# Shematic_servo_light.net
KiCad netlist of a schematic drawn in Altium Designer
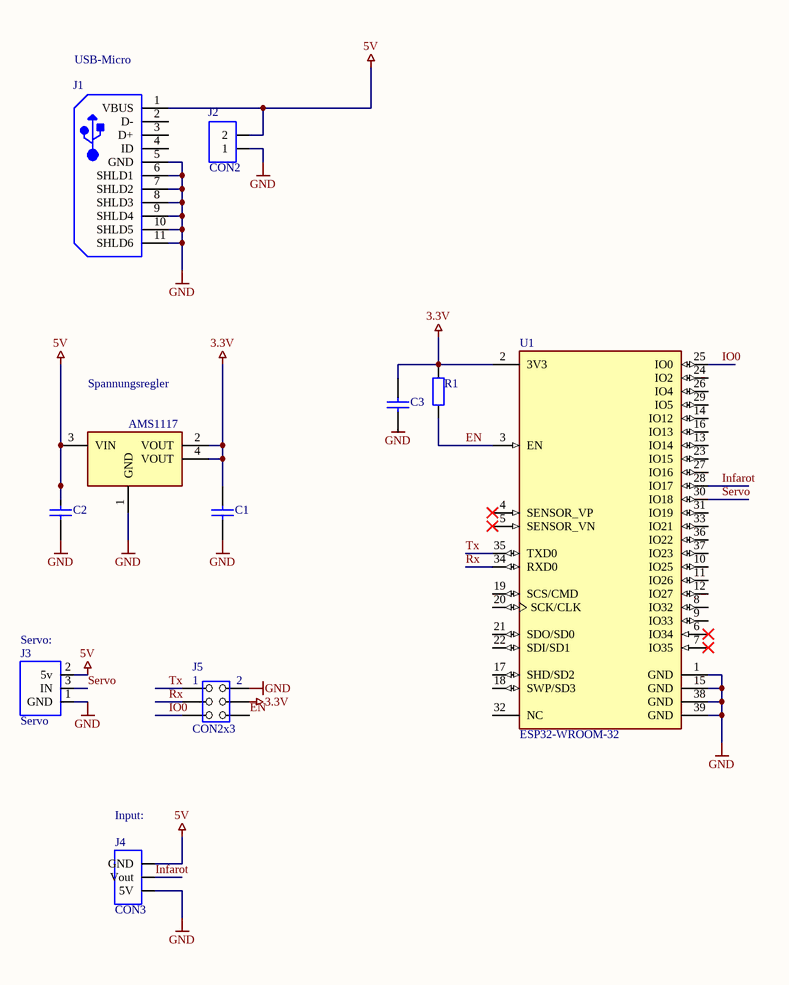
[diagram p0: Shematic_servo_light.SchDoc]

(export (version "E")
  (design (tool "Eeschema 10.0.6"))
  (components
    (comp (ref "C1")
      (value "Cap Ceramic")
      (footprint "0805C")
      (description "Kondensator")
      (libsource (lib "HTL Lib") (part "Cap Ceramic"))
    )
    (comp (ref "C2")
      (value "Cap Ceramic")
      (footprint "0805C")
      (description "Kondensator")
      (libsource (lib "HTL Lib") (part "Cap Ceramic"))
    )
    (comp (ref "C3")
      (value "Cap Ceramic")
      (footprint "0805C")
      (description "Kondensator")
      (libsource (lib "HTL Lib") (part "Cap Ceramic"))
    )
    (comp (ref "J1")
      (value "USB-Micro")
      (footprint "USB-MICRO-B_V - RZEP_CN")
      (description "Right Angle Female Type AB Micro USB Connector, 30 V, 1.8 A, -30 to 85 degC, RoHS, Tape and Reel")
      (fields (field (name "MANUFACTURER") "Molex"))
      (libsource (lib "Rz_RevB") (part "USB_CMP-2000-05610-1"))
    )
    (comp (ref "J2")
      (value "CON2")
      (footprint "SIP-2")
      (description "Stecker")
      (libsource (lib "HTL-sym-2021_04") (part "CON2"))
    )
    (comp (ref "J3")
      (value "Servo")
      (footprint "Sip-3")
      (description "Stecker")
      (libsource (lib "HTL-sym-2021_04") (part "Servo"))
    )
    (comp (ref "J4")
      (value "CON3")
      (footprint "Sip-3")
      (description "Stecker")
      (libsource (lib "HTL Lib") (part "CON3"))
    )
    (comp (ref "J5")
      (value "CON2x3")
      (footprint "PFOSTEN_2x3")
      (description "Stecker")
      (libsource (lib "HTL Lib") (part "CON2x3"))
    )
    (comp (ref "R1")
      (value "Resistor")
      (footprint "0805R")
      (description "Widerstand")
      (libsource (lib "HTL Lib") (part "Resistor"))
    )
    (comp (ref "U1")
      (value "ESP32-WROOM-32")
      (footprint "MODULE_ESP32-WROOM-32")
      (fields (field (name "MF") "Espressif Systems"))
      (libsource (lib "Rz_RevB") (part "ESP32-WROOM-32"))
    )
    (comp (ref "U2")
      (value "AMS1117")
      (footprint "FP-ams1117-IPC_A")
      (libsource (lib "Rz_RevB") (part "AMS1117"))
    )
  )
  (nets
    (net (code "1") (name "/EN") (class "Default")
      (node (ref "J5") (pin "6") (pinfunction "EN_6") (pintype "passive"))
      (node (ref "R1") (pin "2") (pinfunction "2_2") (pintype "passive"))
      (node (ref "U1") (pin "3") (pinfunction "EN_3") (pintype "input"))
    )
    (net (code "2") (name "/IO0") (class "Default")
      (node (ref "J5") (pin "5") (pinfunction "IO0_5") (pintype "passive"))
      (node (ref "U1") (pin "25") (pinfunction "IO0_25") (pintype "bidirectional"))
    )
    (net (code "3") (name "/Infarot") (class "Default")
      (node (ref "J4") (pin "2") (pinfunction "Vout_2") (pintype "passive"))
      (node (ref "U1") (pin "28") (pinfunction "IO17_28") (pintype "bidirectional"))
    )
    (net (code "4") (name "/Rx") (class "Default")
      (node (ref "J5") (pin "3") (pinfunction "Rx_3") (pintype "passive"))
      (node (ref "U1") (pin "34") (pinfunction "RXD0_34") (pintype "bidirectional"))
    )
    (net (code "5") (name "/Servo") (class "Default")
      (node (ref "J3") (pin "3") (pinfunction "IN_3") (pintype "passive"))
      (node (ref "U1") (pin "30") (pinfunction "IO18_30") (pintype "bidirectional"))
    )
    (net (code "6") (name "/Tx") (class "Default")
      (node (ref "J5") (pin "1") (pinfunction "Tx_1") (pintype "passive"))
      (node (ref "U1") (pin "35") (pinfunction "TXD0_35") (pintype "bidirectional"))
    )
    (net (code "7") (name "3.3V") (class "Default")
      (node (ref "C1") (pin "2") (pinfunction "2_2") (pintype "passive"))
      (node (ref "C3") (pin "2") (pinfunction "2_2") (pintype "passive"))
      (node (ref "J5") (pin "4") (pinfunction "3V3_4") (pintype "passive"))
      (node (ref "R1") (pin "1") (pinfunction "1_1") (pintype "passive"))
      (node (ref "U1") (pin "2") (pinfunction "3V3_2") (pintype "power_in"))
      (node (ref "U2") (pin "2") (pinfunction "VOUT_2") (pintype "passive"))
      (node (ref "U2") (pin "4") (pinfunction "VOUT_4") (pintype "passive"))
    )
    (net (code "8") (name "5V") (class "Default")
      (node (ref "C2") (pin "2") (pinfunction "2_2") (pintype "passive"))
      (node (ref "J1") (pin "1") (pinfunction "VBUS_1") (pintype "passive"))
      (node (ref "J2") (pin "2") (pinfunction "2_2") (pintype "passive"))
      (node (ref "J3") (pin "2") (pinfunction "5v_2") (pintype "passive"))
      (node (ref "J4") (pin "3") (pinfunction "GND_3") (pintype "passive"))
      (node (ref "U2") (pin "3") (pinfunction "VIN_3") (pintype "power_in"))
    )
    (net (code "9") (name "GND") (class "Default")
      (node (ref "C1") (pin "1") (pinfunction "1_1") (pintype "passive"))
      (node (ref "C2") (pin "1") (pinfunction "1_1") (pintype "passive"))
      (node (ref "J1") (pin "10") (pinfunction "SHLD5_10") (pintype "passive"))
      (node (ref "J1") (pin "11") (pinfunction "SHLD6_11") (pintype "passive"))
      (node (ref "J1") (pin "5") (pinfunction "GND_5") (pintype "passive"))
      (node (ref "J1") (pin "6") (pinfunction "SHLD1_6") (pintype "passive"))
      (node (ref "J1") (pin "7") (pinfunction "SHLD2_7") (pintype "passive"))
      (node (ref "J1") (pin "8") (pinfunction "SHLD3_8") (pintype "passive"))
      (node (ref "J1") (pin "9") (pinfunction "SHLD4_9") (pintype "passive"))
      (node (ref "J2") (pin "1") (pinfunction "1_1") (pintype "passive"))
      (node (ref "J3") (pin "1") (pinfunction "GND_1") (pintype "passive"))
      (node (ref "J4") (pin "1") (pinfunction "5V_1") (pintype "passive"))
      (node (ref "J5") (pin "2") (pinfunction "GND_2") (pintype "passive"))
      (node (ref "U1") (pin "1") (pinfunction "GND_1") (pintype "power_in"))
      (node (ref "U1") (pin "15") (pinfunction "GND_15") (pintype "power_in"))
      (node (ref "U1") (pin "38") (pinfunction "GND_38") (pintype "power_in"))
      (node (ref "U1") (pin "39") (pinfunction "GND_39") (pintype "power_in"))
      (node (ref "U2") (pin "1") (pinfunction "GND_1") (pintype "power_in"))
    )
    (net (code "10") (name "unconnected-(C3-Pad1)") (class "Default")
      (node (ref "C3") (pin "1") (pinfunction "1_1") (pintype "passive"))
    )
    (net (code "11") (name "unconnected-(J1-D+-Pad3)") (class "Default")
      (node (ref "J1") (pin "3") (pinfunction "D+_3") (pintype "passive"))
    )
    (net (code "12") (name "unconnected-(J1-D--Pad2)") (class "Default")
      (node (ref "J1") (pin "2") (pinfunction "D-_2") (pintype "passive"))
    )
    (net (code "13") (name "unconnected-(J1-ID-Pad4)") (class "Default")
      (node (ref "J1") (pin "4") (pinfunction "ID_4") (pintype "passive"))
    )
    (net (code "14") (name "unconnected-(U1-IO2-Pad24)") (class "Default")
      (node (ref "U1") (pin "24") (pinfunction "IO2_24") (pintype "bidirectional"))
    )
    (net (code "15") (name "unconnected-(U1-IO4-Pad26)") (class "Default")
      (node (ref "U1") (pin "26") (pinfunction "IO4_26") (pintype "bidirectional"))
    )
    (net (code "16") (name "unconnected-(U1-IO5-Pad29)") (class "Default")
      (node (ref "U1") (pin "29") (pinfunction "IO5_29") (pintype "bidirectional"))
    )
    (net (code "17") (name "unconnected-(U1-IO12-Pad14)") (class "Default")
      (node (ref "U1") (pin "14") (pinfunction "IO12_14") (pintype "bidirectional"))
    )
    (net (code "18") (name "unconnected-(U1-IO13-Pad16)") (class "Default")
      (node (ref "U1") (pin "16") (pinfunction "IO13_16") (pintype "bidirectional"))
    )
    (net (code "19") (name "unconnected-(U1-IO14-Pad13)") (class "Default")
      (node (ref "U1") (pin "13") (pinfunction "IO14_13") (pintype "bidirectional"))
    )
    (net (code "20") (name "unconnected-(U1-IO15-Pad23)") (class "Default")
      (node (ref "U1") (pin "23") (pinfunction "IO15_23") (pintype "bidirectional"))
    )
    (net (code "21") (name "unconnected-(U1-IO16-Pad27)") (class "Default")
      (node (ref "U1") (pin "27") (pinfunction "IO16_27") (pintype "bidirectional"))
    )
    (net (code "22") (name "unconnected-(U1-IO19-Pad31)") (class "Default")
      (node (ref "U1") (pin "31") (pinfunction "IO19_31") (pintype "bidirectional"))
    )
    (net (code "23") (name "unconnected-(U1-IO21-Pad33)") (class "Default")
      (node (ref "U1") (pin "33") (pinfunction "IO21_33") (pintype "bidirectional"))
    )
    (net (code "24") (name "unconnected-(U1-IO22-Pad36)") (class "Default")
      (node (ref "U1") (pin "36") (pinfunction "IO22_36") (pintype "bidirectional"))
    )
    (net (code "25") (name "unconnected-(U1-IO23-Pad37)") (class "Default")
      (node (ref "U1") (pin "37") (pinfunction "IO23_37") (pintype "bidirectional"))
    )
    (net (code "26") (name "unconnected-(U1-IO25-Pad10)") (class "Default")
      (node (ref "U1") (pin "10") (pinfunction "IO25_10") (pintype "bidirectional"))
    )
    (net (code "27") (name "unconnected-(U1-IO26-Pad11)") (class "Default")
      (node (ref "U1") (pin "11") (pinfunction "IO26_11") (pintype "bidirectional"))
    )
    (net (code "28") (name "unconnected-(U1-IO27-Pad12)") (class "Default")
      (node (ref "U1") (pin "12") (pinfunction "IO27_12") (pintype "bidirectional"))
    )
    (net (code "29") (name "unconnected-(U1-IO32-Pad8)") (class "Default")
      (node (ref "U1") (pin "8") (pinfunction "IO32_8") (pintype "bidirectional"))
    )
    (net (code "30") (name "unconnected-(U1-IO33-Pad9)") (class "Default")
      (node (ref "U1") (pin "9") (pinfunction "IO33_9") (pintype "bidirectional"))
    )
    (net (code "31") (name "unconnected-(U1-IO34-Pad6)") (class "Default")
      (node (ref "U1") (pin "6") (pinfunction "IO34_6") (pintype "input+no_connect"))
    )
    (net (code "32") (name "unconnected-(U1-IO35-Pad7)") (class "Default")
      (node (ref "U1") (pin "7") (pinfunction "IO35_7") (pintype "input+no_connect"))
    )
    (net (code "33") (name "unconnected-(U1-NC-Pad32)") (class "Default")
      (node (ref "U1") (pin "32") (pinfunction "NC_32") (pintype "passive"))
    )
    (net (code "34") (name "unconnected-(U1-SCK{slash}CLK-Pad20)") (class "Default")
      (node (ref "U1") (pin "20") (pinfunction "SCK/CLK_20") (pintype "bidirectional"))
    )
    (net (code "35") (name "unconnected-(U1-SCS{slash}CMD-Pad19)") (class "Default")
      (node (ref "U1") (pin "19") (pinfunction "SCS/CMD_19") (pintype "bidirectional"))
    )
    (net (code "36") (name "unconnected-(U1-SDI{slash}SD1-Pad22)") (class "Default")
      (node (ref "U1") (pin "22") (pinfunction "SDI/SD1_22") (pintype "bidirectional"))
    )
    (net (code "37") (name "unconnected-(U1-SDO{slash}SD0-Pad21)") (class "Default")
      (node (ref "U1") (pin "21") (pinfunction "SDO/SD0_21") (pintype "bidirectional"))
    )
    (net (code "38") (name "unconnected-(U1-SENSOR_VN-Pad5)") (class "Default")
      (node (ref "U1") (pin "5") (pinfunction "SENSOR_VN_5") (pintype "input+no_connect"))
    )
    (net (code "39") (name "unconnected-(U1-SENSOR_VP-Pad4)") (class "Default")
      (node (ref "U1") (pin "4") (pinfunction "SENSOR_VP_4") (pintype "input+no_connect"))
    )
    (net (code "40") (name "unconnected-(U1-SHD{slash}SD2-Pad17)") (class "Default")
      (node (ref "U1") (pin "17") (pinfunction "SHD/SD2_17") (pintype "bidirectional"))
    )
    (net (code "41") (name "unconnected-(U1-SWP{slash}SD3-Pad18)") (class "Default")
      (node (ref "U1") (pin "18") (pinfunction "SWP/SD3_18") (pintype "bidirectional"))
    )
  )
)
